# ATSAMD11C14A.net
KiCad netlist of a schematic drawn in EAGLE
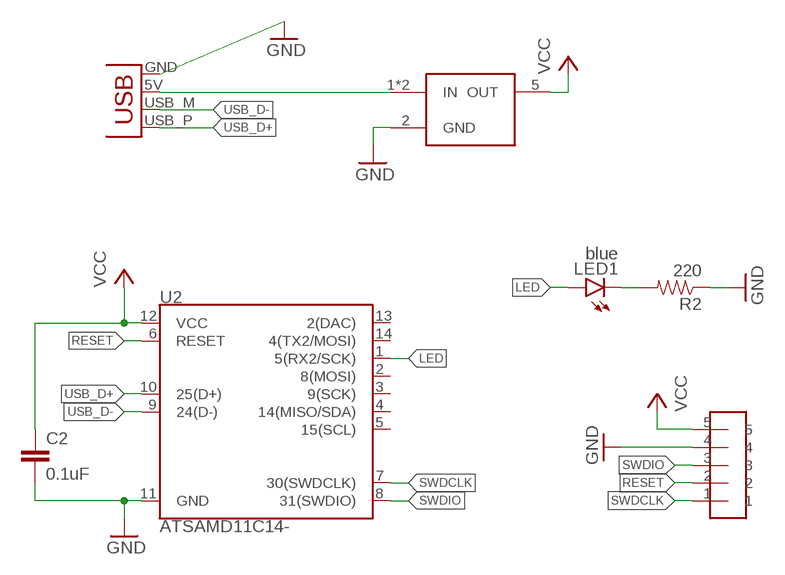
[diagram p0: schematic, sheet 1]

(export (version "E")
  (design (tool "Eeschema 10.0.6"))
  (components
    (comp (ref "C2")
      (value "0.1uF")
      (footprint "eagle-import:0603-CAP")
      (libsource (lib "eagle-import") (part "CAP0603-CAP"))
    )
    (comp (ref "LED1")
      (value "blue")
      (footprint "eagle-import:LED-0603")
      (libsource (lib "eagle-import") (part "LED0603"))
    )
    (comp (ref "R2")
      (value "220")
      (footprint "eagle-import:0603-RES")
      (libsource (lib "eagle-import") (part "RESISTOR0603"))
    )
    (comp (ref "U$1")
      (value "HEADER-5-TESTPOINT")
      (footprint "eagle-import:TESTPOINT-5")
      (libsource (lib "eagle-import") (part "HEADER-5-TESTPOINT"))
    )
    (comp (ref "U$2")
      (value "USB_CONN_UNSHIELDED")
      (footprint "eagle-import:USB-A-PCB")
      (libsource (lib "eagle-import") (part "USB_CONN_UNSHIELDED"))
    )
    (comp (ref "U$3")
      (value "REGULATOR3.3V-0.5A-MIC5219")
      (footprint "eagle-import:SOT23-5")
      (libsource (lib "eagle-import") (part "REGULATOR3.3V-0.5A-MIC5219"))
    )
    (comp (ref "U2")
      (value "ATSAMD11C14-")
      (footprint "eagle-import:SOIC14")
      (libsource (lib "eagle-import") (part "ATSAMD11C14-"))
    )
  )
  (nets
    (net (code "1") (name "GND") (class "Default")
      (node (ref "C2") (pin "2") (pinfunction "2_2") (pintype "passive"))
      (node (ref "R2") (pin "1") (pinfunction "1_1") (pintype "passive"))
      (node (ref "U$1") (pin "4") (pinfunction "4_4") (pintype "bidirectional"))
      (node (ref "U$2") (pin "GND") (pinfunction "GND_GND") (pintype "bidirectional"))
      (node (ref "U$3") (pin "2") (pinfunction "GND_2") (pintype "bidirectional"))
      (node (ref "U2") (pin "11") (pinfunction "GND_11") (pintype "bidirectional"))
    )
    (net (code "2") (name "LED") (class "Default")
      (node (ref "LED1") (pin "A") (pinfunction "A_A") (pintype "passive"))
      (node (ref "U2") (pin "1") (pinfunction "5(RX2/SCK)_1") (pintype "bidirectional"))
    )
    (net (code "3") (name "Net-(LED1-PadC)") (class "Default")
      (node (ref "LED1") (pin "C") (pinfunction "C_C") (pintype "passive"))
      (node (ref "R2") (pin "2") (pinfunction "2_2") (pintype "passive"))
    )
    (net (code "4") (name "Net-(U$2-VBUS)") (class "Default")
      (node (ref "U$2") (pin "5V") (pinfunction "VBUS_5V") (pintype "bidirectional"))
      (node (ref "U$3") (pin "1") (pinfunction "IN_1") (pintype "bidirectional"))
      (node (ref "U$3") (pin "3") (pinfunction "IN_3") (pintype "bidirectional"))
    )
    (net (code "5") (name "RESET") (class "Default")
      (node (ref "U$1") (pin "2") (pinfunction "2_2") (pintype "bidirectional"))
      (node (ref "U2") (pin "6") (pinfunction "RESET_6") (pintype "bidirectional"))
    )
    (net (code "6") (name "SWDCLK") (class "Default")
      (node (ref "U$1") (pin "1") (pinfunction "1_1") (pintype "bidirectional"))
      (node (ref "U2") (pin "7") (pinfunction "30(SWDCLK)_7") (pintype "bidirectional"))
    )
    (net (code "7") (name "SWDIO") (class "Default")
      (node (ref "U$1") (pin "3") (pinfunction "3_3") (pintype "bidirectional"))
      (node (ref "U2") (pin "8") (pinfunction "31(SWDIO)_8") (pintype "bidirectional"))
    )
    (net (code "8") (name "USB_D+") (class "Default")
      (node (ref "U$2") (pin "USB_P") (pinfunction "D+_USB_P") (pintype "bidirectional"))
      (node (ref "U2") (pin "10") (pinfunction "25(D+)_10") (pintype "bidirectional"))
    )
    (net (code "9") (name "USB_D-") (class "Default")
      (node (ref "U$2") (pin "USB_M") (pinfunction "D-_USB_M") (pintype "bidirectional"))
      (node (ref "U2") (pin "9") (pinfunction "24(D-)_9") (pintype "bidirectional"))
    )
    (net (code "10") (name "VCC") (class "Default")
      (node (ref "C2") (pin "1") (pinfunction "1_1") (pintype "passive"))
      (node (ref "U$1") (pin "5") (pinfunction "5_5") (pintype "bidirectional"))
      (node (ref "U$3") (pin "5") (pinfunction "OUT_5") (pintype "bidirectional"))
      (node (ref "U2") (pin "12") (pinfunction "VCC_12") (pintype "bidirectional"))
    )
    (net (code "11") (name "unconnected-(U2-2(DAC)-Pad13)") (class "Default")
      (node (ref "U2") (pin "13") (pinfunction "2(DAC)_13") (pintype "bidirectional"))
    )
    (net (code "12") (name "unconnected-(U2-4(TX2{slash}MOSI)-Pad14)") (class "Default")
      (node (ref "U2") (pin "14") (pinfunction "4(TX2/MOSI)_14") (pintype "bidirectional"))
    )
    (net (code "13") (name "unconnected-(U2-8(MOSI)-Pad2)") (class "Default")
      (node (ref "U2") (pin "2") (pinfunction "8(MOSI)_2") (pintype "bidirectional"))
    )
    (net (code "14") (name "unconnected-(U2-9(SCK)-Pad3)") (class "Default")
      (node (ref "U2") (pin "3") (pinfunction "9(SCK)_3") (pintype "bidirectional"))
    )
    (net (code "15") (name "unconnected-(U2-14(MISO{slash}SDA)-Pad4)") (class "Default")
      (node (ref "U2") (pin "4") (pinfunction "14(MISO/SDA)_4") (pintype "bidirectional"))
    )
    (net (code "16") (name "unconnected-(U2-15(SCL)-Pad5)") (class "Default")
      (node (ref "U2") (pin "5") (pinfunction "15(SCL)_5") (pintype "bidirectional"))
    )
  )
)
